# 12V_Rest.net
KiCad netlist of a schematic drawn in Altium Designer
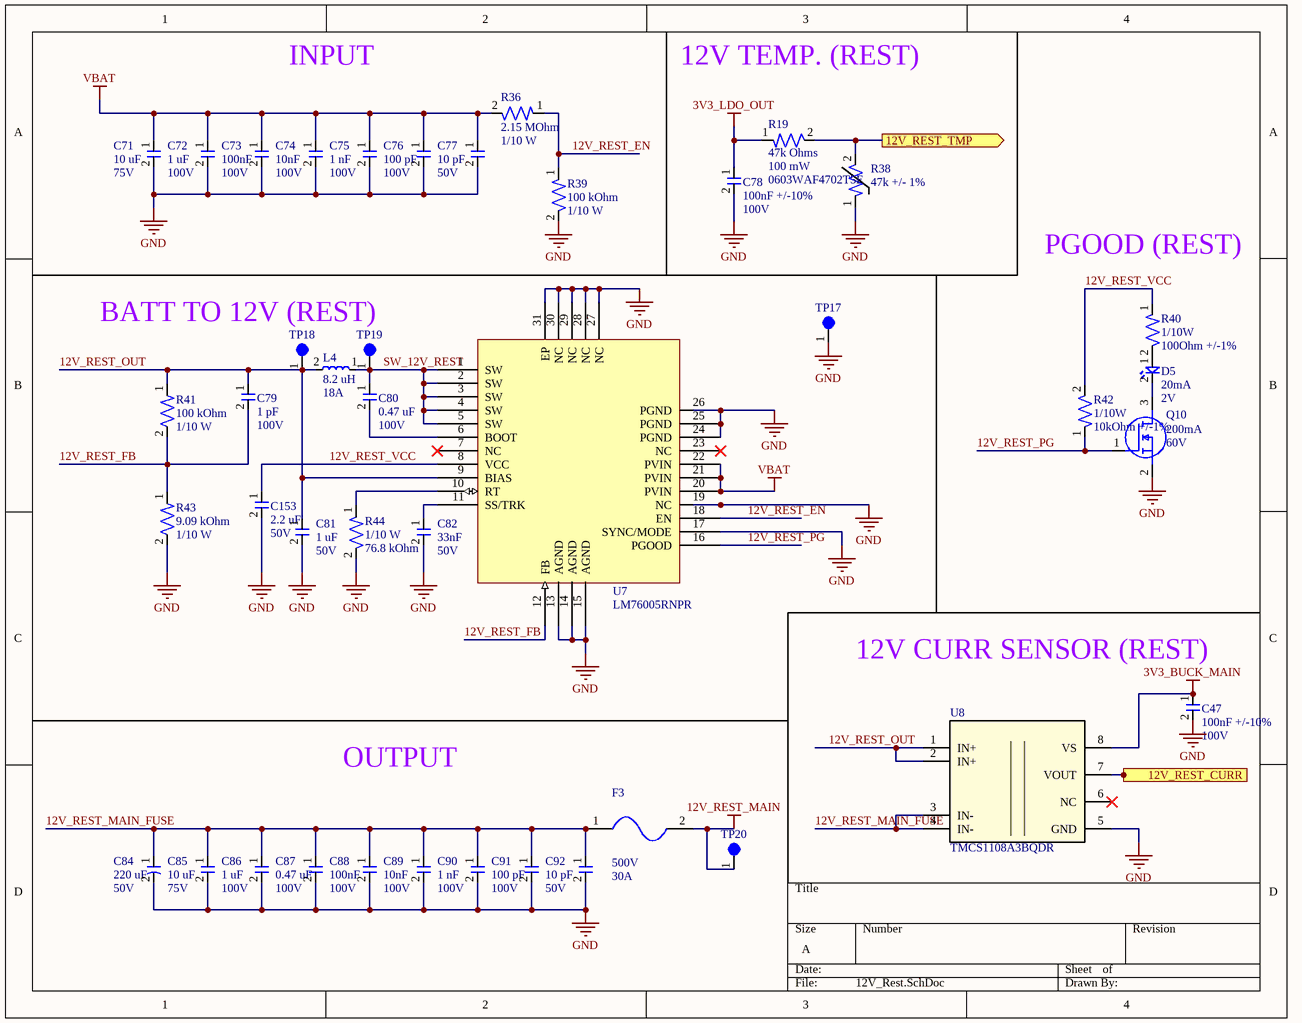
[diagram p0: 12V_Rest.SchDoc]

(export (version "E")
  (design (tool "Eeschema 10.0.6"))
  (components
    (comp (ref "C47")
      (value "CC0603KRX7R0BB104")
      (footprint "CAP-0603")
      (description "CAP CER 0.1UF 100V X7R 0603")
      (fields
        (field (name "MANUFACTURER") "YAGEO")
        (field (name "CAPACITANCE") "100nF +/-10%")
        (field (name "VOLTAGE RATING") "100V")
      )
      (libsource (lib "MasterLib") (part "CAP-100N-0001"))
    )
    (comp (ref "C71")
      (value "C3225X7R1N106K250AC")
      (footprint "CAP-1210")
      (description "10 µF ±10% 75V Ceramic Capacitor X7R 1210 (3225 Metric)")
      (fields (field (name "CAPACITANCE") "10 uF") (field (name "VOLTAGE RATING") "75V"))
      (libsource (lib "MasterLib") (part "CAP-10U-0004"))
    )
    (comp (ref "C72")
      (value "CL31B105KCHNNNE")
      (footprint "CAP-1206 - duplicate")
      (description "1 µF ±10% 100V Ceramic Capacitor X7R 1206 (3216 Metric)")
      (fields (field (name "CAPACITANCE") "1 uF") (field (name "VOLTAGE") "100V"))
      (libsource (lib "MasterLib") (part "CAP-1U-0001"))
    )
    (comp (ref "C73")
      (value "CC0603KRX7R0BB104")
      (footprint "CAP-0603")
      (description "CAP CER 0.1UF 100V X7R 0603")
      (fields
        (field (name "MANUFACTURER") "YAGEO")
        (field (name "CAPACITANCE") "100nF")
        (field (name "VOLTAGE RATING") "100V")
      )
      (libsource (lib "MasterLib") (part "CAP-100N-0001"))
    )
    (comp (ref "C74")
      (value "C1608C0G2A103J080AC")
      (footprint "CAP-0603")
      (description "CAP CER 10000PF 100V C0G 0603")
      (fields
        (field (name "MANUFACTURER") "TDK Corporation")
        (field (name "CAPACITANCE") "10nF")
        (field (name "VOLTAGE RATING") "100V")
      )
      (libsource (lib "MasterLib") (part "CAP-10N-0002"))
    )
    (comp (ref "C75")
      (value "C0603Y102K1RAC7867")
      (footprint "CAP-0603")
      (description "1000 pF ±10% 100V Ceramic Capacitor X7R 0603 (1608 Metric)")
      (fields (field (name "CAPACITANCE") "1 nF") (field (name "VOLTAGE") "100V"))
      (libsource (lib "MasterLib") (part "CAP-1N-0001"))
    )
    (comp (ref "C76")
      (value "0603N101J101CT")
      (footprint "CAP-0603")
      (description "100 pF ±5% 100V Ceramic Capacitor C0G, NP0 0603 (1608 Metric)")
      (fields
        (field (name "TOLERANCE") "+/-5%")
        (field (name "CAPACITANCE") "100 pF")
        (field (name "VOLTAGE") "100V")
      )
      (libsource (lib "MasterLib") (part "CAP-100P-0002"))
    )
    (comp (ref "C77")
      (value "0603N100J500CT")
      (footprint "CAP-0603")
      (description "10 pF ±5% 50V Ceramic Capacitor C0G, NP0 0603 (1608 Metric)")
      (fields
        (field (name "MANUFACTURER") "Walshin Technology Corporation")
        (field (name "CAPACITANCE") "10 pF")
        (field (name "VOLTAGE RATING") "50V")
      )
      (libsource (lib "MasterLib") (part "CAP-10P-0001"))
    )
    (comp (ref "C78")
      (value "CC0603KRX7R0BB104")
      (footprint "CAP-0603")
      (description "CAP CER 0.1UF 100V X7R 0603")
      (fields
        (field (name "MANUFACTURER") "YAGEO")
        (field (name "CAPACITANCE") "100nF +/-10%")
        (field (name "VOLTAGE RATING") "100V")
      )
      (libsource (lib "MasterLib") (part "CAP-100N-0001"))
    )
    (comp (ref "C79")
      (value "885012006087")
      (footprint "CAP-0603")
      (description "1 pF ±0.25pF 100V Ceramic Capacitor C0G, NP0 0603 (1608 Metric)")
      (fields
        (field (name "TOLERANCE") "+/- 0.25 pF")
        (field (name "CAPACITANCE") "1 pF")
        (field (name "VOLTAGE") "100V")
      )
      (libsource (lib "MasterLib") (part "CAP-1P-0001"))
    )
    (comp (ref "C80")
      (value "KAM21KR72A474KL")
      (footprint "CAP-0805")
      (description "0.47 µF ±10% 100V Ceramic Capacitor X7R 0805 (2012 Metric)")
      (fields
        (field (name "TOLERANCE") "+/- 10%")
        (field (name "CAPACITANCE") "0.47 uF")
        (field (name "VOLTAGE") "100V")
      )
      (libsource (lib "MasterLib") (part "CAP-0.47U-0001"))
    )
    (comp (ref "C81")
      (value "UMK107AB7105KA-T")
      (footprint "CAP-0603")
      (description "1 µF ±10% 50V Ceramic Capacitor X7R 0603 (1608 Metric)")
      (fields (field (name "CAPACITANCE") "1 uF") (field (name "VOLTAGE") "50V"))
      (libsource (lib "MasterLib") (part "CAP-1U-0002"))
    )
    (comp (ref "C82")
      (value "CC0603KRX7R9BB333")
      (footprint "CAP-0603")
      (description "0.033 µF ±10% 50V Ceramic Capacitor X7R 0603 (1608 Metric)")
      (fields
        (field (name "MANUFACTURER") "YAGEO")
        (field (name "CAPACITANCE") "33nF")
        (field (name "VOLTAGE RATING") "50V")
      )
      (libsource (lib "MasterLib") (part "CAP-33N-0001"))
    )
    (comp (ref "C84")
      (value "50TZV220M10X10.5")
      (footprint "ELEC-220U-0003")
      (description "220 µF 50 V Aluminum Electrolytic Capacitors Radial, Can - SMD 2000 Hrs @ 105°C")
      (fields (field (name "CAPACITANCE") "220 uF") (field (name "VOLTAGE RATING") "50V"))
      (libsource (lib "MasterLib") (part "ELEC-220U-0003"))
    )
    (comp (ref "C85")
      (value "C3225X7R1N106K250AC")
      (footprint "CAP-1210")
      (description "10 µF ±10% 75V Ceramic Capacitor X7R 1210 (3225 Metric)")
      (fields (field (name "CAPACITANCE") "10 uF") (field (name "VOLTAGE RATING") "75V"))
      (libsource (lib "MasterLib") (part "CAP-10U-0004"))
    )
    (comp (ref "C86")
      (value "CL31B105KCHNNNE")
      (footprint "CAP-1206 - duplicate")
      (description "1 µF ±10% 100V Ceramic Capacitor X7R 1206 (3216 Metric)")
      (fields (field (name "CAPACITANCE") "1 uF") (field (name "VOLTAGE") "100V"))
      (libsource (lib "MasterLib") (part "CAP-1U-0001"))
    )
    (comp (ref "C87")
      (value "KAM21KR72A474KL")
      (footprint "CAP-0805")
      (description "0.47 µF ±10% 100V Ceramic Capacitor X7R 0805 (2012 Metric)")
      (fields
        (field (name "TOLERANCE") "+/- 10%")
        (field (name "CAPACITANCE") "0.47 uF")
        (field (name "VOLTAGE") "100V")
      )
      (libsource (lib "MasterLib") (part "CAP-0.47U-0001"))
    )
    (comp (ref "C88")
      (value "CC0603KRX7R0BB104")
      (footprint "CAP-0603")
      (description "CAP CER 0.1UF 100V X7R 0603")
      (fields
        (field (name "MANUFACTURER") "YAGEO")
        (field (name "CAPACITANCE") "100nF")
        (field (name "VOLTAGE RATING") "100V")
      )
      (libsource (lib "MasterLib") (part "CAP-100N-0001"))
    )
    (comp (ref "C89")
      (value "C1608C0G2A103J080AC")
      (footprint "CAP-0603")
      (description "CAP CER 10000PF 100V C0G 0603")
      (fields
        (field (name "MANUFACTURER") "TDK Corporation")
        (field (name "CAPACITANCE") "10nF")
        (field (name "VOLTAGE RATING") "100V")
      )
      (libsource (lib "MasterLib") (part "CAP-10N-0002"))
    )
    (comp (ref "C90")
      (value "C0603Y102K1RAC7867")
      (footprint "CAP-0603")
      (description "1000 pF ±10% 100V Ceramic Capacitor X7R 0603 (1608 Metric)")
      (fields (field (name "CAPACITANCE") "1 nF") (field (name "VOLTAGE") "100V"))
      (libsource (lib "MasterLib") (part "CAP-1N-0001"))
    )
    (comp (ref "C91")
      (value "0603N101J101CT")
      (footprint "CAP-0603")
      (description "100 pF ±5% 100V Ceramic Capacitor C0G, NP0 0603 (1608 Metric)")
      (fields
        (field (name "TOLERANCE") "+/-5%")
        (field (name "CAPACITANCE") "100 pF")
        (field (name "VOLTAGE") "100V")
      )
      (libsource (lib "MasterLib") (part "CAP-100P-0002"))
    )
    (comp (ref "C92")
      (value "0603N100J500CT")
      (footprint "CAP-0603")
      (description "10 pF ±5% 50V Ceramic Capacitor C0G, NP0 0603 (1608 Metric)")
      (fields
        (field (name "MANUFACTURER") "Walshin Technology Corporation")
        (field (name "CAPACITANCE") "10 pF")
        (field (name "VOLTAGE RATING") "50V")
      )
      (libsource (lib "MasterLib") (part "CAP-10P-0001"))
    )
    (comp (ref "C153")
      (value "UMK107BBJ225KA-T")
      (footprint "CAP-0603")
      (description "2.2 µF ±10% 50V Ceramic Capacitor X5R 0603 (1608 Metric)")
      (fields (field (name "CAPACITANCE") "2.2 uF") (field (name "OLTAGE") "50V"))
      (libsource (lib "MasterLib") (part "CAP-2.2U-0001"))
    )
    (comp (ref "D5")
      (value "150060AS75000")
      (footprint "LED-0603")
      (description "CAP CER 0.1UF 100V X7R 0603")
      (fields
        (field (name "MANUFACTURER") "Wurth Electronik")
        (field (name "CURRENT RATING") "20mA")
        (field (name "VF") "2V")
      )
      (libsource (lib "MasterLib") (part "LED_Amber_0001"))
    )
    (comp (ref "F3")
      (value "3568")
      (footprint "FUSE-ATM-0001")
      (description "Fuse Holder 30 A 500V 1 Circuit Blade Through Hole")
      (fields (field (name "VOLTAGE RATING") "500V") (field (name "CURRENT") "30A"))
      (libsource (lib "MasterLib") (part "FUSE-ATM-0001"))
    )
    (comp (ref "L4")
      (value "IHLP6767GZER8R2M01")
      (footprint "PWRIND-8.2U-0002")
      (description "8.2 µH Shielded Molded Inductor 18 A 10.66mOhm Max Nonstandard")
      (fields
        (field (name "TOLERANCE") "+/-20%")
        (field (name "INDUCTANCE") "8.2 uH")
        (field (name "DCI") "18A")
      )
      (libsource (lib "MasterLib") (part "PWRIND-8.2U-0002"))
    )
    (comp (ref "Q10")
      (value "T2N7002AK,LM")
      (footprint "NMOS-SOT23-3")
      (description "MOSFET N-CH 60V 200MA SOT23")
      (fields
        (field (name "MANUFACTURER") "Toshiba")
        (field (name "ID-CONTINUOUS") "200mA")
        (field (name "VDS-MAX") "60V")
      )
      (libsource (lib "MasterLib") (part "NMOS-200MA-0001"))
    )
    (comp (ref "R19")
      (value "0603WAF4702T5E")
      (footprint "RES-0603")
      (description "100mW Thick Film Resistors 75V ±100ppm/℃ ±1% 47kΩ 0603 Chip Resistor - Surface Mount ROHS")
      (fields (field (name "POWER") "100mW"))
      (libsource (lib "MasterLib") (part "RES-47k-0001-JLC"))
    )
    (comp (ref "R36")
      (value "RC0603FR-072M15L")
      (footprint "RES-0603")
      (description "2.15 MOhms ±1% 0.1W, 1/10W Chip Resistor 0603 (1608 Metric) Moisture Resistant Thick Film")
      (fields
        (field (name "TOLERANCE") "+/-1%")
        (field (name "RESISTANCE") "2.15 MOhm")
        (field (name "POWER") "1/10 W")
      )
      (libsource (lib "MasterLib") (part "RES-2.15M-0001"))
    )
    (comp (ref "R38")
      (value "TMP6431DECR")
      (footprint "RES-0402")
      (description "PTC Thermistor 47 kOhms 0402 (1006 Metric)")
      (fields (field (name "MANUFACTURER") "Texas Instruments") (field (name "RESISTANCE") "47k +/- 1%"))
      (libsource (lib "MasterLib") (part "THERM-47K-0001"))
    )
    (comp (ref "R39")
      (value "RC0603FR-07100KL")
      (footprint "RES-0603")
      (description "100 kOhms ±1% 0.1W, 1/10W Chip Resistor 0603 (1608 Metric) Moisture Resistant Thick Film")
      (fields
        (field (name "TOLERANCE") "+/- 1%")
        (field (name "RESISTANCE") "100 kOhm")
        (field (name "POWER") "1/10 W")
      )
      (libsource (lib "MasterLib") (part "RES-100K-0003"))
    )
    (comp (ref "R40")
      (value "AC0603FR-10100RL")
      (footprint "RES-0603")
      (description "100 Ohms ±1% 0.1W, 1/10W Chip Resistor 0603 (1608 Metric) Automotive AEC-Q200 Thick Film")
      (fields
        (field (name "MANUFACTURER") "YAGEO")
        (field (name "POWER RATING") "1/10W")
        (field (name "RESISTANCE") "100Ohm +/-1%")
      )
      (libsource (lib "MasterLib") (part "RES-100-0002"))
    )
    (comp (ref "R41")
      (value "RC0603FR-07100KL")
      (footprint "RES-0603")
      (description "100 kOhms ±1% 0.1W, 1/10W Chip Resistor 0603 (1608 Metric) Moisture Resistant Thick Film")
      (fields
        (field (name "TOLERANCE") "+/- 1%")
        (field (name "RESISTANCE") "100 kOhm")
        (field (name "POWER") "1/10 W")
      )
      (libsource (lib "MasterLib") (part "RES-100K-0003"))
    )
    (comp (ref "R42")
      (value "RC0603FR-0710KP")
      (footprint "RES-0603")
      (description "RES SMD 10K OHM 1% 1/10W 0603")
      (fields
        (field (name "MANUFACTURER") "YAGEO")
        (field (name "POWER RATING") "1/10W")
        (field (name "RESISTANCE") "10kOhm +/-1%")
      )
      (libsource (lib "MasterLib") (part "RES-10K-0002"))
    )
    (comp (ref "R43")
      (value "RC0603FR-079K09L")
      (footprint "RES-0603")
      (description "9.09 kOhms ±1% 0.1W, 1/10W Chip Resistor 0603 (1608 Metric) Moisture Resistant Thick Film")
      (fields
        (field (name "TOLERANCE") "+/-1%")
        (field (name "RESISTANCE") "9.09 kOhm")
        (field (name "POWER") "1/10 W")
      )
      (libsource (lib "MasterLib") (part "RES-9.09K-0001"))
    )
    (comp (ref "R44")
      (value "RC0603FR-0776K8L")
      (footprint "RES-0603")
      (description "76.8 kOhms ±1% 0.1W, 1/10W Chip Resistor 0603 (1608 Metric) Moisture Resistant Thick Film")
      (fields
        (field (name "MANUFACTURER") "Yageo")
        (field (name "TOLERANCE") "+/- 1%")
        (field (name "POWER") "1/10 W")
        (field (name "RESISTANCE") "76.8 kOhm")
      )
      (libsource (lib "MasterLib") (part "RES-76.8K-0001"))
    )
    (comp (ref "TP17")
      (value "5003")
      (footprint "TEST-POINT-0001")
      (description "Oranange PC Test Point, Miniature Phoisphor Bronze Silver Plating Through Hole Mounting Type")
      (libsource (lib "MasterLib") (part "TEST-POINT-0001"))
    )
    (comp (ref "TP18")
      (value "5003")
      (footprint "TEST-POINT-0001")
      (description "Oranange PC Test Point, Miniature Phoisphor Bronze Silver Plating Through Hole Mounting Type")
      (libsource (lib "MasterLib") (part "TEST-POINT-0001"))
    )
    (comp (ref "TP19")
      (value "5003")
      (footprint "TEST-POINT-0001")
      (description "Oranange PC Test Point, Miniature Phoisphor Bronze Silver Plating Through Hole Mounting Type")
      (libsource (lib "MasterLib") (part "TEST-POINT-0001"))
    )
    (comp (ref "TP20")
      (value "5003")
      (footprint "TEST-POINT-0001")
      (description "Oranange PC Test Point, Miniature Phoisphor Bronze Silver Plating Through Hole Mounting Type")
      (libsource (lib "MasterLib") (part "TEST-POINT-0001"))
    )
    (comp (ref "U7")
      (value "LM76005RNPR")
      (footprint "IC-30-WQFN(6x4)")
      (description "Buck Switching Regulator IC Positive Adjustable 1V 1 Output 5A 30-WFQFN Exposed Pad")
      (fields (field (name "MANUFACTURER") "Texas Instruments") (field (name "CURRENT") "LM76005RNPR"))
      (libsource (lib "MasterLib") (part "IC-BUCK-0006"))
    )
    (comp (ref "U8")
      (value "TMCS1108A3BQDR")
      (footprint "D0008A-IPC_A")
      (libsource (lib "MasterLib") (part "IC-CURRENT-0005"))
    )
  )
  (nets
    (net (code "1") (name "/12V_REST_CURR") (class "Default")
      (node (ref "U8") (pin "7") (pinfunction "VOUT_7") (pintype "passive"))
    )
    (net (code "2") (name "/12V_REST_EN") (class "Default")
      (node (ref "R36") (pin "1") (pinfunction "1_1") (pintype "passive"))
      (node (ref "R39") (pin "1") (pinfunction "1_1") (pintype "passive"))
      (node (ref "U7") (pin "18") (pinfunction "EN_18") (pintype "power_in"))
    )
    (net (code "3") (name "/12V_REST_FB") (class "Default")
      (node (ref "C79") (pin "2") (pinfunction "2_2") (pintype "passive"))
      (node (ref "R41") (pin "2") (pinfunction "2_2") (pintype "passive"))
      (node (ref "R43") (pin "1") (pinfunction "1_1") (pintype "passive"))
      (node (ref "U7") (pin "12") (pinfunction "FB_12") (pintype "input"))
    )
    (net (code "4") (name "/12V_REST_MAIN_FUSE") (class "Default")
      (node (ref "C84") (pin "1") (pinfunction "1_1") (pintype "passive"))
      (node (ref "C85") (pin "1") (pinfunction "1_1") (pintype "passive"))
      (node (ref "C86") (pin "1") (pinfunction "1_1") (pintype "passive"))
      (node (ref "C87") (pin "1") (pinfunction "1_1") (pintype "passive"))
      (node (ref "C88") (pin "1") (pinfunction "1_1") (pintype "passive"))
      (node (ref "C89") (pin "1") (pinfunction "1_1") (pintype "passive"))
      (node (ref "C90") (pin "1") (pinfunction "1_1") (pintype "passive"))
      (node (ref "C91") (pin "1") (pinfunction "1_1") (pintype "passive"))
      (node (ref "C92") (pin "1") (pinfunction "1_1") (pintype "passive"))
      (node (ref "F3") (pin "1") (pinfunction "0_1") (pintype "passive"))
      (node (ref "U8") (pin "3") (pinfunction "IN-_3") (pintype "passive"))
      (node (ref "U8") (pin "4") (pinfunction "IN-_4") (pintype "passive"))
    )
    (net (code "5") (name "/12V_REST_OUT") (class "Default")
      (node (ref "C79") (pin "1") (pinfunction "1_1") (pintype "passive"))
      (node (ref "C81") (pin "1") (pinfunction "1_1") (pintype "passive"))
      (node (ref "L4") (pin "2") (pinfunction "2_2") (pintype "passive"))
      (node (ref "R41") (pin "1") (pinfunction "1_1") (pintype "passive"))
      (node (ref "TP18") (pin "1") (pinfunction "0_1") (pintype "passive"))
      (node (ref "U7") (pin "9") (pinfunction "BIAS_9") (pintype "power_in"))
      (node (ref "U8") (pin "1") (pinfunction "IN+_1") (pintype "passive"))
      (node (ref "U8") (pin "2") (pinfunction "IN+_2") (pintype "passive"))
    )
    (net (code "6") (name "/12V_REST_PG") (class "Default")
      (node (ref "Q10") (pin "1") (pinfunction "G_1") (pintype "passive"))
      (node (ref "R42") (pin "1") (pinfunction "1_1") (pintype "passive"))
      (node (ref "U7") (pin "16") (pinfunction "PGOOD_16") (pintype "power_in"))
    )
    (net (code "7") (name "/12V_REST_TMP") (class "Default")
      (node (ref "R19") (pin "2") (pinfunction "2_2") (pintype "passive"))
      (node (ref "R38") (pin "2") (pinfunction "2_2") (pintype "passive"))
    )
    (net (code "8") (name "/12V_REST_VCC") (class "Default")
      (node (ref "C153") (pin "1") (pinfunction "1_1") (pintype "passive"))
      (node (ref "R40") (pin "1") (pinfunction "1_1") (pintype "passive"))
      (node (ref "R42") (pin "2") (pinfunction "2_2") (pintype "passive"))
      (node (ref "U7") (pin "8") (pinfunction "VCC_8") (pintype "power_in"))
    )
    (net (code "9") (name "/SW_12V_REST") (class "Default")
      (node (ref "C80") (pin "1") (pinfunction "1_1") (pintype "passive"))
      (node (ref "L4") (pin "1") (pinfunction "1_1") (pintype "passive"))
      (node (ref "TP19") (pin "1") (pinfunction "0_1") (pintype "passive"))
      (node (ref "U7") (pin "1") (pinfunction "SW_1") (pintype "power_in"))
      (node (ref "U7") (pin "2") (pinfunction "SW_2") (pintype "power_in"))
      (node (ref "U7") (pin "3") (pinfunction "SW_3") (pintype "power_in"))
      (node (ref "U7") (pin "4") (pinfunction "SW_4") (pintype "power_in"))
      (node (ref "U7") (pin "5") (pinfunction "SW_5") (pintype "power_in"))
    )
    (net (code "10") (name "3V3_BUCK_MAIN") (class "Default")
      (node (ref "C47") (pin "1") (pinfunction "1_1") (pintype "passive"))
      (node (ref "U8") (pin "8") (pinfunction "VS_8") (pintype "power_in"))
    )
    (net (code "11") (name "3V3_LDO_OUT") (class "Default")
      (node (ref "C78") (pin "1") (pinfunction "1_1") (pintype "passive"))
      (node (ref "R19") (pin "1") (pinfunction "1_1") (pintype "passive"))
    )
    (net (code "12") (name "12V_REST_MAIN") (class "Default")
      (node (ref "F3") (pin "2") (pinfunction "1_2") (pintype "passive"))
      (node (ref "TP20") (pin "1") (pinfunction "0_1") (pintype "passive"))
    )
    (net (code "13") (name "GND") (class "Default")
      (node (ref "C153") (pin "2") (pinfunction "2_2") (pintype "passive"))
      (node (ref "C47") (pin "2") (pinfunction "2_2") (pintype "passive"))
      (node (ref "C71") (pin "2") (pinfunction "2_2") (pintype "passive"))
      (node (ref "C72") (pin "2") (pinfunction "2_2") (pintype "passive"))
      (node (ref "C73") (pin "2") (pinfunction "2_2") (pintype "passive"))
      (node (ref "C74") (pin "2") (pinfunction "2_2") (pintype "passive"))
      (node (ref "C75") (pin "2") (pinfunction "2_2") (pintype "passive"))
      (node (ref "C76") (pin "2") (pinfunction "2_2") (pintype "passive"))
      (node (ref "C77") (pin "2") (pinfunction "2_2") (pintype "passive"))
      (node (ref "C78") (pin "2") (pinfunction "2_2") (pintype "passive"))
      (node (ref "C81") (pin "2") (pinfunction "2_2") (pintype "passive"))
      (node (ref "C82") (pin "2") (pinfunction "2_2") (pintype "passive"))
      (node (ref "C84") (pin "2") (pinfunction "2_2") (pintype "passive"))
      (node (ref "C85") (pin "2") (pinfunction "2_2") (pintype "passive"))
      (node (ref "C86") (pin "2") (pinfunction "2_2") (pintype "passive"))
      (node (ref "C87") (pin "2") (pinfunction "2_2") (pintype "passive"))
      (node (ref "C88") (pin "2") (pinfunction "2_2") (pintype "passive"))
      (node (ref "C89") (pin "2") (pinfunction "2_2") (pintype "passive"))
      (node (ref "C90") (pin "2") (pinfunction "2_2") (pintype "passive"))
      (node (ref "C91") (pin "2") (pinfunction "2_2") (pintype "passive"))
      (node (ref "C92") (pin "2") (pinfunction "2_2") (pintype "passive"))
      (node (ref "Q10") (pin "2") (pinfunction "S_2") (pintype "passive"))
      (node (ref "R38") (pin "1") (pinfunction "1_1") (pintype "passive"))
      (node (ref "R39") (pin "2") (pinfunction "2_2") (pintype "passive"))
      (node (ref "R43") (pin "2") (pinfunction "2_2") (pintype "passive"))
      (node (ref "R44") (pin "2") (pinfunction "2_2") (pintype "passive"))
      (node (ref "TP17") (pin "1") (pinfunction "0_1") (pintype "passive"))
      (node (ref "U7") (pin "13") (pinfunction "AGND_13") (pintype "power_in"))
      (node (ref "U7") (pin "14") (pinfunction "AGND_14") (pintype "power_in"))
      (node (ref "U7") (pin "15") (pinfunction "AGND_15") (pintype "power_in"))
      (node (ref "U7") (pin "17") (pinfunction "SYNC/MODE_17") (pintype "power_in"))
      (node (ref "U7") (pin "19") (pinfunction "NC_19") (pintype "power_in"))
      (node (ref "U7") (pin "24") (pinfunction "PGND_24") (pintype "power_in"))
      (node (ref "U7") (pin "25") (pinfunction "PGND_25") (pintype "power_in"))
      (node (ref "U7") (pin "26") (pinfunction "PGND_26") (pintype "power_in"))
      (node (ref "U7") (pin "27") (pinfunction "NC_27") (pintype "power_in"))
      (node (ref "U7") (pin "28") (pinfunction "NC_28") (pintype "power_in"))
      (node (ref "U7") (pin "29") (pinfunction "NC_29") (pintype "power_in"))
      (node (ref "U7") (pin "30") (pinfunction "NC_30") (pintype "power_in"))
      (node (ref "U7") (pin "31") (pinfunction "EP_31") (pintype "power_in"))
      (node (ref "U8") (pin "5") (pinfunction "GND_5") (pintype "power_in"))
    )
    (net (code "14") (name "Net-(D5-Pad1)") (class "Default")
      (node (ref "D5") (pin "1") (pinfunction "1_1") (pintype "passive"))
      (node (ref "R40") (pin "2") (pinfunction "2_2") (pintype "passive"))
    )
    (net (code "15") (name "Net-(Q10-D)") (class "Default")
      (node (ref "D5") (pin "2") (pinfunction "2_2") (pintype "passive"))
      (node (ref "Q10") (pin "3") (pinfunction "D_3") (pintype "passive"))
    )
    (net (code "16") (name "Net-(U7-BOOT)") (class "Default")
      (node (ref "C80") (pin "2") (pinfunction "2_2") (pintype "passive"))
      (node (ref "U7") (pin "6") (pinfunction "BOOT_6") (pintype "power_in"))
    )
    (net (code "17") (name "Net-(U7-RT)") (class "Default")
      (node (ref "R44") (pin "1") (pinfunction "1_1") (pintype "passive"))
      (node (ref "U7") (pin "10") (pinfunction "RT_10") (pintype "bidirectional"))
    )
    (net (code "18") (name "Net-(U7-SS{slash}TRK)") (class "Default")
      (node (ref "C82") (pin "1") (pinfunction "1_1") (pintype "passive"))
      (node (ref "U7") (pin "11") (pinfunction "SS/TRK_11") (pintype "passive"))
    )
    (net (code "19") (name "VBAT") (class "Default")
      (node (ref "C71") (pin "1") (pinfunction "1_1") (pintype "passive"))
      (node (ref "C72") (pin "1") (pinfunction "1_1") (pintype "passive"))
      (node (ref "C73") (pin "1") (pinfunction "1_1") (pintype "passive"))
      (node (ref "C74") (pin "1") (pinfunction "1_1") (pintype "passive"))
      (node (ref "C75") (pin "1") (pinfunction "1_1") (pintype "passive"))
      (node (ref "C76") (pin "1") (pinfunction "1_1") (pintype "passive"))
      (node (ref "C77") (pin "1") (pinfunction "1_1") (pintype "passive"))
      (node (ref "R36") (pin "2") (pinfunction "2_2") (pintype "passive"))
      (node (ref "U7") (pin "20") (pinfunction "PVIN_20") (pintype "power_in"))
      (node (ref "U7") (pin "21") (pinfunction "PVIN_21") (pintype "power_in"))
      (node (ref "U7") (pin "22") (pinfunction "PVIN_22") (pintype "power_in"))
    )
    (net (code "20") (name "unconnected-(U7-NC-Pad7)") (class "Default")
      (node (ref "U7") (pin "7") (pinfunction "NC_7") (pintype "power_in+no_connect"))
    )
    (net (code "21") (name "unconnected-(U7-NC-Pad23)") (class "Default")
      (node (ref "U7") (pin "23") (pinfunction "NC_23") (pintype "tri_state+no_connect"))
    )
    (net (code "22") (name "unconnected-(U8-NC-Pad6)") (class "Default")
      (node (ref "U8") (pin "6") (pinfunction "NC_6") (pintype "passive+no_connect"))
    )
  )
)
